# D8_schematic.net
KiCad netlist of a schematic drawn in EAGLE
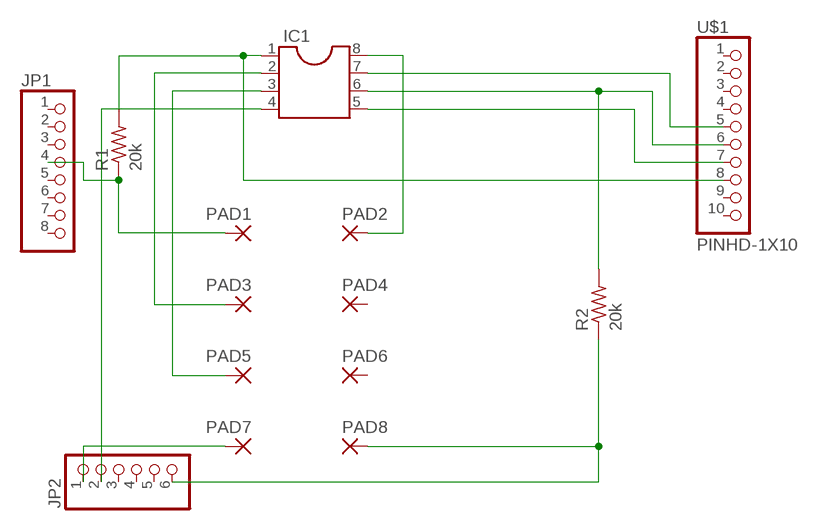
[diagram p0: schematic, sheet 1]

(export (version "E")
  (design (tool "Eeschema 10.0.6"))
  (components
    (comp (ref "IC1")
      (value "DIL8S")
      (footprint "eagle-import:SOCKET-08")
      (libsource (lib "eagle-import") (part "DIL8S"))
    )
    (comp (ref "JP1")
      (value "PINHD-1X8-3.5MM")
      (footprint "eagle-import:1X08-3.5MM")
      (libsource (lib "eagle-import") (part "PINHD-1X8-3.5MM"))
    )
    (comp (ref "JP2")
      (value "PINHD-1X6-3.5MM")
      (footprint "eagle-import:1X06-3.5MM")
      (libsource (lib "eagle-import") (part "PINHD-1X6-3.5MM"))
    )
    (comp (ref "PAD1")
      (value "1,6/0,8")
      (footprint "eagle-import:1,6_0,8")
      (libsource (lib "eagle-import") (part "1,6/0,8"))
    )
    (comp (ref "PAD2")
      (value "1,6/0,8")
      (footprint "eagle-import:1,6_0,8")
      (libsource (lib "eagle-import") (part "1,6/0,8"))
    )
    (comp (ref "PAD3")
      (value "1,6/0,8")
      (footprint "eagle-import:1,6_0,8")
      (libsource (lib "eagle-import") (part "1,6/0,8"))
    )
    (comp (ref "PAD4")
      (value "1,6/0,8")
      (footprint "eagle-import:1,6_0,8")
      (libsource (lib "eagle-import") (part "1,6/0,8"))
    )
    (comp (ref "PAD5")
      (value "1,6/0,8")
      (footprint "eagle-import:1,6_0,8")
      (libsource (lib "eagle-import") (part "1,6/0,8"))
    )
    (comp (ref "PAD6")
      (value "1,6/0,8")
      (footprint "eagle-import:1,6_0,8")
      (libsource (lib "eagle-import") (part "1,6/0,8"))
    )
    (comp (ref "PAD7")
      (value "1,6/0,8")
      (footprint "eagle-import:1,6_0,8")
      (libsource (lib "eagle-import") (part "1,6/0,8"))
    )
    (comp (ref "PAD8")
      (value "1,6/0,8")
      (footprint "eagle-import:1,6_0,8")
      (libsource (lib "eagle-import") (part "1,6/0,8"))
    )
    (comp (ref "R1")
      (value "20k")
      (footprint "eagle-import:0309_10")
      (libsource (lib "eagle-import") (part "R-US_0309/10"))
    )
    (comp (ref "R2")
      (value "20k")
      (footprint "eagle-import:0309_10")
      (libsource (lib "eagle-import") (part "R-US_0309/10"))
    )
    (comp (ref "U$1")
      (value "PINHD-1X10")
      (footprint "eagle-import:1X10-BIG")
      (libsource (lib "eagle-import") (part "PINHD-1X10"))
    )
  )
  (nets
    (net (code "1") (name "Net-(IC1-Pad1)") (class "Default")
      (node (ref "IC1") (pin "1") (pinfunction "1_1") (pintype "passive"))
      (node (ref "R1") (pin "2") (pinfunction "2_2") (pintype "passive"))
      (node (ref "U$1") (pin "8") (pinfunction "8_8") (pintype "passive"))
    )
    (net (code "2") (name "Net-(IC1-Pad4)") (class "Default")
      (node (ref "IC1") (pin "4") (pinfunction "4_4") (pintype "passive"))
      (node (ref "JP2") (pin "2") (pinfunction "2_2") (pintype "passive"))
    )
    (net (code "3") (name "Net-(IC1-Pad5)") (class "Default")
      (node (ref "IC1") (pin "5") (pinfunction "5_5") (pintype "passive"))
      (node (ref "U$1") (pin "7") (pinfunction "7_7") (pintype "passive"))
    )
    (net (code "4") (name "Net-(IC1-Pad6)") (class "Default")
      (node (ref "IC1") (pin "6") (pinfunction "6_6") (pintype "passive"))
      (node (ref "R2") (pin "2") (pinfunction "2_2") (pintype "passive"))
      (node (ref "U$1") (pin "6") (pinfunction "6_6") (pintype "passive"))
    )
    (net (code "5") (name "Net-(IC1-Pad7)") (class "Default")
      (node (ref "IC1") (pin "7") (pinfunction "7_7") (pintype "passive"))
      (node (ref "U$1") (pin "5") (pinfunction "5_5") (pintype "passive"))
    )
    (net (code "6") (name "Net-(PAD1-P)") (class "Default")
      (node (ref "JP1") (pin "4") (pinfunction "4_4") (pintype "passive"))
      (node (ref "PAD1") (pin "1") (pinfunction "P_1") (pintype "passive"))
      (node (ref "R1") (pin "1") (pinfunction "1_1") (pintype "passive"))
    )
    (net (code "7") (name "Net-(PAD2-P)") (class "Default")
      (node (ref "IC1") (pin "8") (pinfunction "8_8") (pintype "passive"))
      (node (ref "PAD2") (pin "1") (pinfunction "P_1") (pintype "passive"))
    )
    (net (code "8") (name "Net-(PAD3-P)") (class "Default")
      (node (ref "IC1") (pin "2") (pinfunction "2_2") (pintype "passive"))
      (node (ref "PAD3") (pin "1") (pinfunction "P_1") (pintype "passive"))
    )
    (net (code "9") (name "Net-(PAD5-P)") (class "Default")
      (node (ref "IC1") (pin "3") (pinfunction "3_3") (pintype "passive"))
      (node (ref "PAD5") (pin "1") (pinfunction "P_1") (pintype "passive"))
    )
    (net (code "10") (name "Net-(PAD7-P)") (class "Default")
      (node (ref "JP2") (pin "1") (pinfunction "1_1") (pintype "passive"))
      (node (ref "PAD7") (pin "1") (pinfunction "P_1") (pintype "passive"))
    )
    (net (code "11") (name "Net-(PAD8-P)") (class "Default")
      (node (ref "JP2") (pin "6") (pinfunction "6_6") (pintype "passive"))
      (node (ref "PAD8") (pin "1") (pinfunction "P_1") (pintype "passive"))
      (node (ref "R2") (pin "1") (pinfunction "1_1") (pintype "passive"))
    )
    (net (code "12") (name "unconnected-(JP1-Pad1)") (class "Default")
      (node (ref "JP1") (pin "1") (pinfunction "1_1") (pintype "passive"))
    )
    (net (code "13") (name "unconnected-(JP1-Pad2)") (class "Default")
      (node (ref "JP1") (pin "2") (pinfunction "2_2") (pintype "passive"))
    )
    (net (code "14") (name "unconnected-(JP1-Pad3)") (class "Default")
      (node (ref "JP1") (pin "3") (pinfunction "3_3") (pintype "passive"))
    )
    (net (code "15") (name "unconnected-(JP1-Pad5)") (class "Default")
      (node (ref "JP1") (pin "5") (pinfunction "5_5") (pintype "passive"))
    )
    (net (code "16") (name "unconnected-(JP1-Pad6)") (class "Default")
      (node (ref "JP1") (pin "6") (pinfunction "6_6") (pintype "passive"))
    )
    (net (code "17") (name "unconnected-(JP1-Pad7)") (class "Default")
      (node (ref "JP1") (pin "7") (pinfunction "7_7") (pintype "passive"))
    )
    (net (code "18") (name "unconnected-(JP1-Pad8)") (class "Default")
      (node (ref "JP1") (pin "8") (pinfunction "8_8") (pintype "passive"))
    )
    (net (code "19") (name "unconnected-(JP2-Pad3)") (class "Default")
      (node (ref "JP2") (pin "3") (pinfunction "3_3") (pintype "passive"))
    )
    (net (code "20") (name "unconnected-(JP2-Pad4)") (class "Default")
      (node (ref "JP2") (pin "4") (pinfunction "4_4") (pintype "passive"))
    )
    (net (code "21") (name "unconnected-(JP2-Pad5)") (class "Default")
      (node (ref "JP2") (pin "5") (pinfunction "5_5") (pintype "passive"))
    )
    (net (code "22") (name "unconnected-(PAD4-P-Pad1)") (class "Default")
      (node (ref "PAD4") (pin "1") (pinfunction "P_1") (pintype "passive"))
    )
    (net (code "23") (name "unconnected-(PAD6-P-Pad1)") (class "Default")
      (node (ref "PAD6") (pin "1") (pinfunction "P_1") (pintype "passive"))
    )
    (net (code "24") (name "unconnected-(U$1-Pad1)") (class "Default")
      (node (ref "U$1") (pin "1") (pinfunction "1_1") (pintype "passive"))
    )
    (net (code "25") (name "unconnected-(U$1-Pad2)") (class "Default")
      (node (ref "U$1") (pin "2") (pinfunction "2_2") (pintype "passive"))
    )
    (net (code "26") (name "unconnected-(U$1-Pad3)") (class "Default")
      (node (ref "U$1") (pin "3") (pinfunction "3_3") (pintype "passive"))
    )
    (net (code "27") (name "unconnected-(U$1-Pad4)") (class "Default")
      (node (ref "U$1") (pin "4") (pinfunction "4_4") (pintype "passive"))
    )
    (net (code "28") (name "unconnected-(U$1-Pad9)") (class "Default")
      (node (ref "U$1") (pin "9") (pinfunction "9_9") (pintype "passive"))
    )
    (net (code "29") (name "unconnected-(U$1-Pad10)") (class "Default")
      (node (ref "U$1") (pin "10") (pinfunction "10_10") (pintype "passive"))
    )
  )
)
